# PART_2.net
KiCad netlist of a schematic drawn in Altium Designer
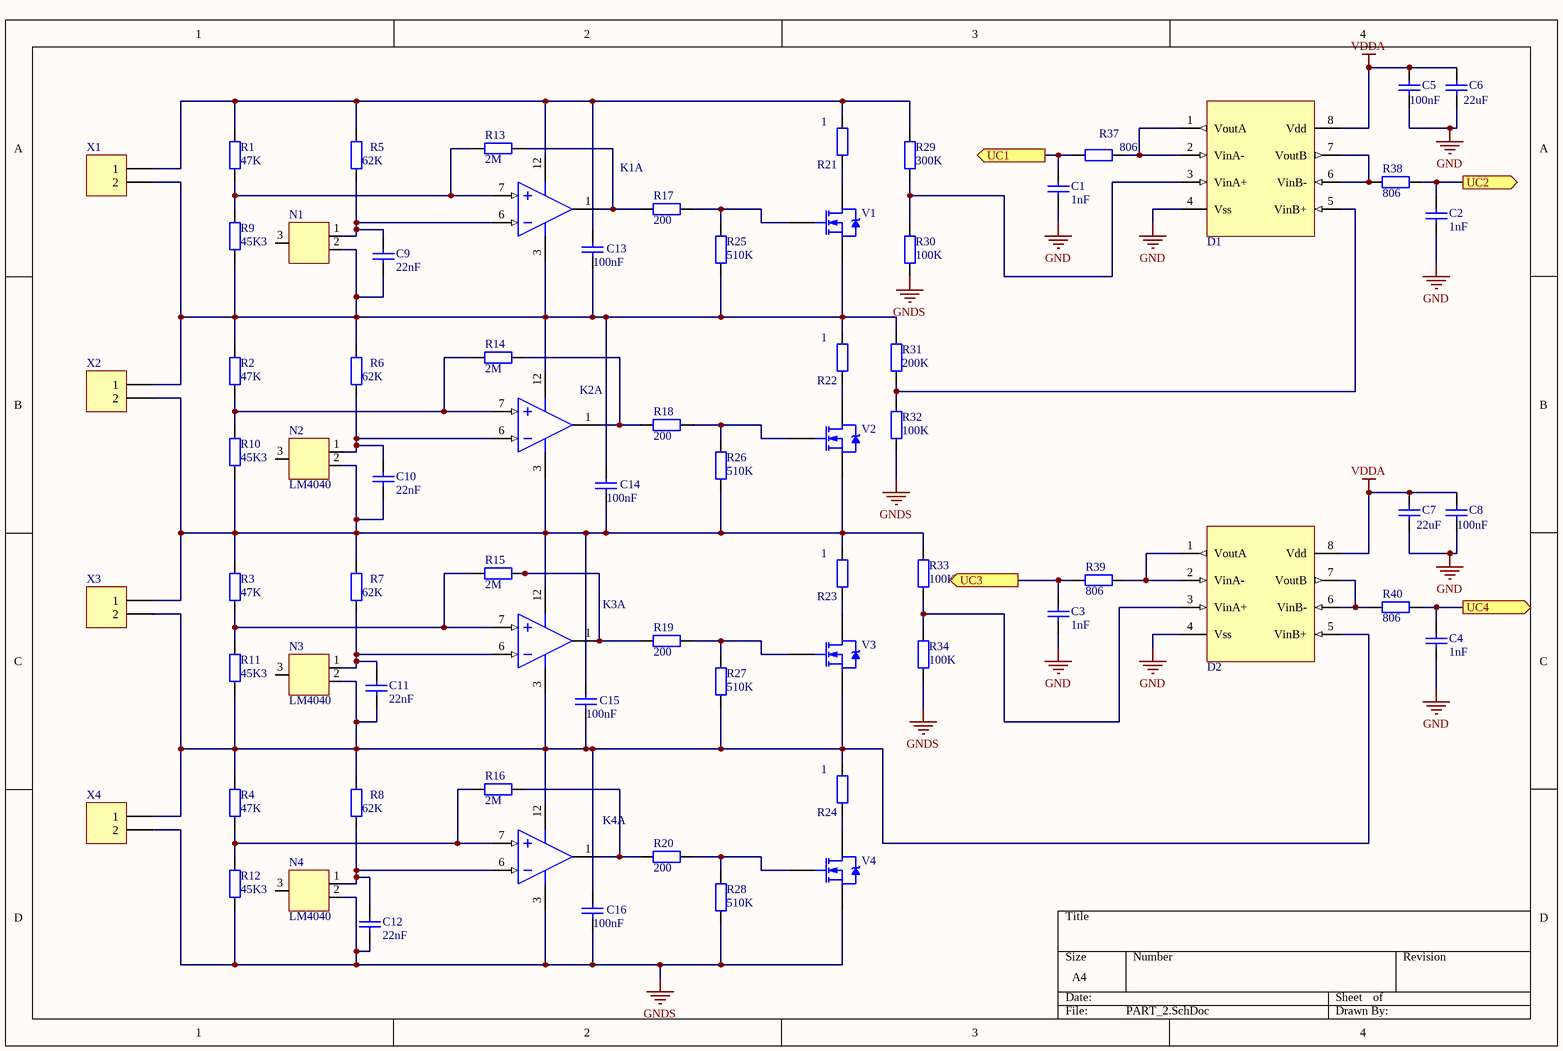
[diagram p0: PART_2.SchDoc]

(export (version "E")
  (design (tool "Eeschema 10.0.6"))
  (components
    (comp (ref "C1")
      (value "1nF")
      (footprint "C0805")
      (description "Capacitor")
      (fields (field (name "Comment") "Cap"))
      (libsource (lib "Miscellaneous Devices") (part "Cap"))
    )
    (comp (ref "C2")
      (value "1nF")
      (footprint "C0805")
      (description "Capacitor")
      (fields (field (name "Comment") "Cap"))
      (libsource (lib "Miscellaneous Devices") (part "Cap"))
    )
    (comp (ref "C3")
      (value "1nF")
      (footprint "C0805")
      (description "Capacitor")
      (fields (field (name "Comment") "Cap"))
      (libsource (lib "Miscellaneous Devices") (part "Cap"))
    )
    (comp (ref "C4")
      (value "1nF")
      (footprint "C0805")
      (description "Capacitor")
      (fields (field (name "Comment") "Cap"))
      (libsource (lib "Miscellaneous Devices") (part "Cap"))
    )
    (comp (ref "C5")
      (value "100nF")
      (footprint "C0805")
      (description "Capacitor")
      (libsource (lib "Miscellaneous Devices") (part "Cap"))
    )
    (comp (ref "C6")
      (value "22uF")
      (footprint "C0805")
      (description "Capacitor")
      (libsource (lib "Miscellaneous Devices") (part "Cap"))
    )
    (comp (ref "C7")
      (value "22uF")
      (footprint "C0805")
      (description "Capacitor")
      (libsource (lib "Miscellaneous Devices") (part "Cap"))
    )
    (comp (ref "C8")
      (value "100nF")
      (footprint "C0805")
      (description "Capacitor")
      (libsource (lib "Miscellaneous Devices") (part "Cap"))
    )
    (comp (ref "C9")
      (value "22nF")
      (footprint "C0805")
      (description "Capacitor")
      (fields (field (name "Comment") "Cap"))
      (libsource (lib "Miscellaneous Devices") (part "Cap"))
    )
    (comp (ref "C10")
      (value "22nF")
      (footprint "C0805")
      (description "Capacitor")
      (fields (field (name "Comment") "Cap"))
      (libsource (lib "Miscellaneous Devices") (part "Cap"))
    )
    (comp (ref "C11")
      (value "22nF")
      (footprint "C0805")
      (description "Capacitor")
      (fields (field (name "Comment") "Cap"))
      (libsource (lib "Miscellaneous Devices") (part "Cap"))
    )
    (comp (ref "C12")
      (value "22nF")
      (footprint "C0805")
      (description "Capacitor")
      (fields (field (name "Comment") "Cap"))
      (libsource (lib "Miscellaneous Devices") (part "Cap"))
    )
    (comp (ref "C13")
      (value "100nF")
      (footprint "C0805")
      (description "Capacitor")
      (fields (field (name "Comment") "Cap"))
      (libsource (lib "Miscellaneous Devices") (part "Cap"))
    )
    (comp (ref "C14")
      (value "100nF")
      (footprint "C0805")
      (description "Capacitor")
      (fields (field (name "Comment") "Cap"))
      (libsource (lib "Miscellaneous Devices") (part "Cap"))
    )
    (comp (ref "C15")
      (value "100nF")
      (footprint "C0805")
      (description "Capacitor")
      (fields (field (name "Comment") "Cap"))
      (libsource (lib "Miscellaneous Devices") (part "Cap"))
    )
    (comp (ref "C16")
      (value "100nF")
      (footprint "C0805")
      (description "Capacitor")
      (fields (field (name "Comment") "Cap"))
      (libsource (lib "Miscellaneous Devices") (part "Cap"))
    )
    (comp (ref "D1")
      (value "~")
      (footprint "MSOP za op.pojacalo")
      (libsource (lib "komponente") (part "Amplifier"))
    )
    (comp (ref "D2")
      (value "~")
      (footprint "MSOP za op.pojacalo")
      (libsource (lib "komponente") (part "Amplifier"))
    )
    (comp (ref "K1")
      (value "TLC3704QJ")
      (footprint "TSSOP5-3")
      (description "Low Power Quad Differential Comparator")
      (libsource (lib "TI Analog Comparator") (part "LP2901D"))
    )
    (comp (ref "K2")
      (value "TLC3704QJ")
      (footprint "TSSOP5-3")
      (description "Low Power Quad Differential Comparator")
      (libsource (lib "TI Analog Comparator") (part "LP2901D"))
    )
    (comp (ref "K3")
      (value "TLC3704QJ")
      (footprint "TSSOP5-3")
      (description "Low Power Quad Differential Comparator")
      (libsource (lib "TI Analog Comparator") (part "LP2901D"))
    )
    (comp (ref "K4")
      (value "TLC3704QJ")
      (footprint "TSSOP5-3")
      (description "Low Power Quad Differential Comparator")
      (libsource (lib "TI Analog Comparator") (part "LP2901D"))
    )
    (comp (ref "N1")
      (value "~")
      (footprint "SOT-23-ref_chip")
      (libsource (lib "komponente") (part "referentni chip"))
    )
    (comp (ref "N2")
      (value "LM4040")
      (footprint "SOT-23-ref_chip")
      (libsource (lib "komponente") (part "referentni chip"))
    )
    (comp (ref "N3")
      (value "LM4040")
      (footprint "SOT-23-ref_chip")
      (libsource (lib "komponente") (part "referentni chip"))
    )
    (comp (ref "N4")
      (value "LM4040")
      (footprint "SOT-23-ref_chip")
      (libsource (lib "komponente") (part "referentni chip"))
    )
    (comp (ref "R1")
      (value "47K")
      (footprint "C0805")
      (description "Resistor")
      (libsource (lib "") (part "Res2_1"))
    )
    (comp (ref "R2")
      (value "47K")
      (footprint "C0805")
      (description "Resistor")
      (libsource (lib "") (part "Res2_1"))
    )
    (comp (ref "R3")
      (value "47K")
      (footprint "C0805")
      (description "Resistor")
      (libsource (lib "") (part "Res2_1"))
    )
    (comp (ref "R4")
      (value "47K")
      (footprint "C0805")
      (description "Resistor")
      (libsource (lib "") (part "Res2_1"))
    )
    (comp (ref "R5")
      (value "62K")
      (footprint "C0805")
      (description "Resistor")
      (libsource (lib "") (part "Res2_1"))
    )
    (comp (ref "R6")
      (value "62K")
      (footprint "C0805")
      (description "Resistor")
      (libsource (lib "") (part "Res2_1"))
    )
    (comp (ref "R7")
      (value "62K")
      (footprint "C0805")
      (description "Resistor")
      (libsource (lib "") (part "Res2_1"))
    )
    (comp (ref "R8")
      (value "62K")
      (footprint "C0805")
      (description "Resistor")
      (libsource (lib "") (part "Res2_1"))
    )
    (comp (ref "R9")
      (value "45K3")
      (footprint "C0805")
      (description "Resistor")
      (libsource (lib "") (part "Res2_1"))
    )
    (comp (ref "R10")
      (value "45K3")
      (footprint "C0805")
      (description "Resistor")
      (libsource (lib "") (part "Res2_1"))
    )
    (comp (ref "R11")
      (value "45K3")
      (footprint "C0805")
      (description "Resistor")
      (libsource (lib "") (part "Res2_1"))
    )
    (comp (ref "R12")
      (value "45K3")
      (footprint "C0805")
      (description "Resistor")
      (libsource (lib "") (part "Res2_1"))
    )
    (comp (ref "R13")
      (value "2M")
      (footprint "C0805")
      (description "Resistor")
      (libsource (lib "Miscellaneous Devices") (part "Res2"))
    )
    (comp (ref "R14")
      (value "2M")
      (footprint "C0805")
      (description "Resistor")
      (libsource (lib "Miscellaneous Devices") (part "Res2"))
    )
    (comp (ref "R15")
      (value "2M")
      (footprint "C0805")
      (description "Resistor")
      (libsource (lib "Miscellaneous Devices") (part "Res2"))
    )
    (comp (ref "R16")
      (value "2M")
      (footprint "C0805")
      (description "Resistor")
      (libsource (lib "Miscellaneous Devices") (part "Res2"))
    )
    (comp (ref "R17")
      (value "200")
      (footprint "C0805")
      (description "Resistor")
      (libsource (lib "Miscellaneous Devices") (part "Res2"))
    )
    (comp (ref "R18")
      (value "200")
      (footprint "C0805")
      (description "Resistor")
      (libsource (lib "Miscellaneous Devices") (part "Res2"))
    )
    (comp (ref "R19")
      (value "200")
      (footprint "C0805")
      (description "Resistor")
      (libsource (lib "Miscellaneous Devices") (part "Res2"))
    )
    (comp (ref "R20")
      (value "200")
      (footprint "C0805")
      (description "Resistor")
      (libsource (lib "Miscellaneous Devices") (part "Res2"))
    )
    (comp (ref "R21")
      (value "1")
      (footprint "F za 7W otpornik")
      (description "Resistor")
      (libsource (lib "") (part "Res2_1"))
    )
    (comp (ref "R22")
      (value "1")
      (footprint "F za 7W otpornik")
      (description "Resistor")
      (libsource (lib "") (part "Res2_1"))
    )
    (comp (ref "R23")
      (value "1")
      (footprint "F za 7W otpornik")
      (description "Resistor")
      (libsource (lib "") (part "Res2_1"))
    )
    (comp (ref "R24")
      (value "1")
      (footprint "F za 7W otpornik")
      (description "Resistor")
      (libsource (lib "") (part "Res2_1"))
    )
    (comp (ref "R25")
      (value "510K")
      (footprint "C0805")
      (description "Resistor")
      (libsource (lib "") (part "Res2_1"))
    )
    (comp (ref "R26")
      (value "510K")
      (footprint "C0805")
      (description "Resistor")
      (libsource (lib "") (part "Res2_1"))
    )
    (comp (ref "R27")
      (value "510K")
      (footprint "C0805")
      (description "Resistor")
      (libsource (lib "") (part "Res2_1"))
    )
    (comp (ref "R28")
      (value "510K")
      (footprint "C0805")
      (description "Resistor")
      (libsource (lib "") (part "Res2_1"))
    )
    (comp (ref "R29")
      (value "300K")
      (footprint "C0805")
      (description "Resistor")
      (libsource (lib "") (part "Res2_1"))
    )
    (comp (ref "R30")
      (value "100K")
      (footprint "C0805")
      (description "Resistor")
      (libsource (lib "") (part "Res2_1"))
    )
    (comp (ref "R31")
      (value "200K")
      (footprint "C0805")
      (description "Resistor")
      (libsource (lib "") (part "Res2_1"))
    )
    (comp (ref "R32")
      (value "100K")
      (footprint "C0805")
      (description "Resistor")
      (libsource (lib "") (part "Res2_1"))
    )
    (comp (ref "R33")
      (value "100K")
      (footprint "C0805")
      (description "Resistor")
      (libsource (lib "") (part "Res2_1"))
    )
    (comp (ref "R34")
      (value "100K")
      (footprint "C0805")
      (description "Resistor")
      (libsource (lib "") (part "Res2_1"))
    )
    (comp (ref "R37")
      (value "806")
      (footprint "C0805")
      (description "Resistor")
      (libsource (lib "Miscellaneous Devices") (part "Res2"))
    )
    (comp (ref "R38")
      (value "806")
      (footprint "C0805")
      (description "Resistor")
      (libsource (lib "") (part "Res2_2"))
    )
    (comp (ref "R39")
      (value "806")
      (footprint "C0805")
      (description "Resistor")
      (libsource (lib "") (part "Res2_2"))
    )
    (comp (ref "R40")
      (value "806")
      (footprint "C0805")
      (description "Resistor")
      (libsource (lib "") (part "Res2_2"))
    )
    (comp (ref "V1")
      (value "NMOS-2")
      (footprint "sot23_transistors")
      (description "N-Channel Power MOSFET")
      (libsource (lib "Miscellaneous Devices") (part "NMOS-2"))
    )
    (comp (ref "V2")
      (value "NMOS-2")
      (footprint "sot23_transistors")
      (description "N-Channel Power MOSFET")
      (libsource (lib "Miscellaneous Devices") (part "NMOS-2"))
    )
    (comp (ref "V3")
      (value "NMOS-2")
      (footprint "sot23_transistors")
      (description "N-Channel Power MOSFET")
      (libsource (lib "Miscellaneous Devices") (part "NMOS-2"))
    )
    (comp (ref "V4")
      (value "NMOS-2")
      (footprint "sot23_transistors")
      (description "N-Channel Power MOSFET")
      (libsource (lib "Miscellaneous Devices") (part "NMOS-2"))
    )
    (comp (ref "X1")
      (value "Header 2")
      (footprint "F Header 1x2")
      (description "Header, 2-Pin")
      (libsource (lib "Miscellaneous Connectors") (part "Header 2"))
    )
    (comp (ref "X2")
      (value "Header 2")
      (footprint "F Header 1x2")
      (description "Header, 2-Pin")
      (libsource (lib "Miscellaneous Connectors") (part "Header 2"))
    )
    (comp (ref "X3")
      (value "Header 2")
      (footprint "F Header 1x2")
      (description "Header, 2-Pin")
      (libsource (lib "Miscellaneous Connectors") (part "Header 2"))
    )
    (comp (ref "X4")
      (value "Header 2")
      (footprint "F Header 1x2")
      (description "Header, 2-Pin")
      (libsource (lib "Miscellaneous Connectors") (part "Header 2"))
    )
  )
  (nets
    (net (code "1") (name "/UC1") (class "Default")
      (node (ref "C1") (pin "2") (pinfunction "2_2") (pintype "passive"))
      (node (ref "R37") (pin "2") (pinfunction "2_2") (pintype "passive"))
    )
    (net (code "2") (name "/UC2") (class "Default")
      (node (ref "C2") (pin "2") (pinfunction "2_2") (pintype "passive"))
      (node (ref "R38") (pin "2") (pinfunction "2_2") (pintype "passive"))
    )
    (net (code "3") (name "/UC3") (class "Default")
      (node (ref "C3") (pin "2") (pinfunction "2_2") (pintype "passive"))
      (node (ref "R39") (pin "1") (pinfunction "1_1") (pintype "passive"))
    )
    (net (code "4") (name "/UC4") (class "Default")
      (node (ref "C4") (pin "2") (pinfunction "2_2") (pintype "passive"))
      (node (ref "R40") (pin "2") (pinfunction "2_2") (pintype "passive"))
    )
    (net (code "5") (name "GND") (class "Default")
      (node (ref "C1") (pin "1") (pinfunction "1_1") (pintype "passive"))
      (node (ref "C2") (pin "1") (pinfunction "1_1") (pintype "passive"))
      (node (ref "C3") (pin "1") (pinfunction "1_1") (pintype "passive"))
      (node (ref "C4") (pin "1") (pinfunction "1_1") (pintype "passive"))
      (node (ref "C5") (pin "1") (pinfunction "1_1") (pintype "passive"))
      (node (ref "C6") (pin "1") (pinfunction "1_1") (pintype "passive"))
      (node (ref "C7") (pin "1") (pinfunction "1_1") (pintype "passive"))
      (node (ref "C8") (pin "1") (pinfunction "1_1") (pintype "passive"))
      (node (ref "D1") (pin "4") (pinfunction "Vss_4") (pintype "power_in"))
      (node (ref "D2") (pin "4") (pinfunction "Vss_4") (pintype "power_in"))
    )
    (net (code "6") (name "GNDS") (class "Default")
      (node (ref "C12") (pin "1") (pinfunction "1_1") (pintype "passive"))
      (node (ref "C16") (pin "2") (pinfunction "2_2") (pintype "passive"))
      (node (ref "K4") (pin "3") (pinfunction "V+_3") (pintype "passive"))
      (node (ref "N4") (pin "2") (pinfunction "2_2") (pintype "passive"))
      (node (ref "R12") (pin "1") (pinfunction "1_1") (pintype "passive"))
      (node (ref "R28") (pin "1") (pinfunction "1_1") (pintype "passive"))
      (node (ref "R30") (pin "1") (pinfunction "1_1") (pintype "passive"))
      (node (ref "R32") (pin "1") (pinfunction "1_1") (pintype "passive"))
      (node (ref "R34") (pin "1") (pinfunction "1_1") (pintype "passive"))
      (node (ref "V4") (pin "3") (pinfunction "S_3") (pintype "passive"))
      (node (ref "X4") (pin "2") (pinfunction "2_2") (pintype "passive"))
    )
    (net (code "7") (name "Net-(D1-VinA+)") (class "Default")
      (node (ref "D1") (pin "3") (pinfunction "VinA+_3") (pintype "input"))
      (node (ref "R29") (pin "1") (pinfunction "1_1") (pintype "passive"))
      (node (ref "R30") (pin "2") (pinfunction "2_2") (pintype "passive"))
    )
    (net (code "8") (name "Net-(D1-VinA-)") (class "Default")
      (node (ref "D1") (pin "1") (pinfunction "VoutA_1") (pintype "output"))
      (node (ref "D1") (pin "2") (pinfunction "VinA-_2") (pintype "input"))
      (node (ref "R37") (pin "1") (pinfunction "1_1") (pintype "passive"))
    )
    (net (code "9") (name "Net-(D1-VinB+)") (class "Default")
      (node (ref "D1") (pin "5") (pinfunction "VinB+_5") (pintype "input"))
      (node (ref "R31") (pin "1") (pinfunction "1_1") (pintype "passive"))
      (node (ref "R32") (pin "2") (pinfunction "2_2") (pintype "passive"))
    )
    (net (code "10") (name "Net-(D1-VinB-)") (class "Default")
      (node (ref "D1") (pin "6") (pinfunction "VinB-_6") (pintype "input"))
      (node (ref "D1") (pin "7") (pinfunction "VoutB_7") (pintype "output"))
      (node (ref "R38") (pin "1") (pinfunction "1_1") (pintype "passive"))
    )
    (net (code "11") (name "Net-(D2-VinA+)") (class "Default")
      (node (ref "D2") (pin "3") (pinfunction "VinA+_3") (pintype "input"))
      (node (ref "R33") (pin "1") (pinfunction "1_1") (pintype "passive"))
      (node (ref "R34") (pin "2") (pinfunction "2_2") (pintype "passive"))
    )
    (net (code "12") (name "Net-(D2-VinA-)") (class "Default")
      (node (ref "D2") (pin "1") (pinfunction "VoutA_1") (pintype "output"))
      (node (ref "D2") (pin "2") (pinfunction "VinA-_2") (pintype "input"))
      (node (ref "R39") (pin "2") (pinfunction "2_2") (pintype "passive"))
    )
    (net (code "13") (name "Net-(D2-VinB+)") (class "Default")
      (node (ref "C11") (pin "1") (pinfunction "1_1") (pintype "passive"))
      (node (ref "C15") (pin "2") (pinfunction "2_2") (pintype "passive"))
      (node (ref "C16") (pin "1") (pinfunction "1_1") (pintype "passive"))
      (node (ref "D2") (pin "5") (pinfunction "VinB+_5") (pintype "input"))
      (node (ref "K3") (pin "3") (pinfunction "V+_3") (pintype "passive"))
      (node (ref "K4") (pin "12") (pinfunction "V-_12") (pintype "passive"))
      (node (ref "N3") (pin "2") (pinfunction "2_2") (pintype "passive"))
      (node (ref "R11") (pin "1") (pinfunction "1_1") (pintype "passive"))
      (node (ref "R24") (pin "2") (pinfunction "2_2") (pintype "passive"))
      (node (ref "R27") (pin "1") (pinfunction "1_1") (pintype "passive"))
      (node (ref "R4") (pin "2") (pinfunction "2_2") (pintype "passive"))
      (node (ref "R8") (pin "2") (pinfunction "2_2") (pintype "passive"))
      (node (ref "V3") (pin "3") (pinfunction "S_3") (pintype "passive"))
      (node (ref "X3") (pin "2") (pinfunction "2_2") (pintype "passive"))
      (node (ref "X4") (pin "1") (pinfunction "1_1") (pintype "passive"))
    )
    (net (code "14") (name "Net-(D2-VinB-)") (class "Default")
      (node (ref "D2") (pin "6") (pinfunction "VinB-_6") (pintype "input"))
      (node (ref "D2") (pin "7") (pinfunction "VoutB_7") (pintype "output"))
      (node (ref "R40") (pin "1") (pinfunction "1_1") (pintype "passive"))
    )
    (net (code "15") (name "Net-(K1A-IN+)") (class "Default")
      (node (ref "K1") (pin "7") (pinfunction "IN+_7") (pintype "input"))
      (node (ref "R1") (pin "1") (pinfunction "1_1") (pintype "passive"))
      (node (ref "R13") (pin "2") (pinfunction "2_2") (pintype "passive"))
      (node (ref "R9") (pin "2") (pinfunction "2_2") (pintype "passive"))
    )
    (net (code "16") (name "Net-(K1A-IN-)") (class "Default")
      (node (ref "C9") (pin "2") (pinfunction "2_2") (pintype "passive"))
      (node (ref "K1") (pin "6") (pinfunction "IN-_6") (pintype "input"))
      (node (ref "N1") (pin "1") (pinfunction "1_1") (pintype "bidirectional"))
      (node (ref "R5") (pin "1") (pinfunction "1_1") (pintype "passive"))
    )
    (net (code "17") (name "Net-(K1A-OUT)") (class "Default")
      (node (ref "K1") (pin "1") (pinfunction "OUT_1") (pintype "open_collector"))
      (node (ref "R13") (pin "1") (pinfunction "1_1") (pintype "passive"))
      (node (ref "R17") (pin "2") (pinfunction "2_2") (pintype "passive"))
    )
    (net (code "18") (name "Net-(K1A-V+)") (class "Default")
      (node (ref "C13") (pin "2") (pinfunction "2_2") (pintype "passive"))
      (node (ref "C14") (pin "1") (pinfunction "1_1") (pintype "passive"))
      (node (ref "C9") (pin "1") (pinfunction "1_1") (pintype "passive"))
      (node (ref "K1") (pin "3") (pinfunction "V+_3") (pintype "passive"))
      (node (ref "K2") (pin "12") (pinfunction "V-_12") (pintype "passive"))
      (node (ref "N1") (pin "2") (pinfunction "2_2") (pintype "passive"))
      (node (ref "R2") (pin "2") (pinfunction "2_2") (pintype "passive"))
      (node (ref "R22") (pin "2") (pinfunction "2_2") (pintype "passive"))
      (node (ref "R25") (pin "1") (pinfunction "1_1") (pintype "passive"))
      (node (ref "R31") (pin "2") (pinfunction "2_2") (pintype "passive"))
      (node (ref "R6") (pin "2") (pinfunction "2_2") (pintype "passive"))
      (node (ref "R9") (pin "1") (pinfunction "1_1") (pintype "passive"))
      (node (ref "V1") (pin "3") (pinfunction "S_3") (pintype "passive"))
      (node (ref "X1") (pin "2") (pinfunction "2_2") (pintype "passive"))
      (node (ref "X2") (pin "1") (pinfunction "1_1") (pintype "passive"))
    )
    (net (code "19") (name "Net-(K1A-V-)") (class "Default")
      (node (ref "C13") (pin "1") (pinfunction "1_1") (pintype "passive"))
      (node (ref "K1") (pin "12") (pinfunction "V-_12") (pintype "passive"))
      (node (ref "R1") (pin "2") (pinfunction "2_2") (pintype "passive"))
      (node (ref "R21") (pin "2") (pinfunction "2_2") (pintype "passive"))
      (node (ref "R29") (pin "2") (pinfunction "2_2") (pintype "passive"))
      (node (ref "R5") (pin "2") (pinfunction "2_2") (pintype "passive"))
      (node (ref "X1") (pin "1") (pinfunction "1_1") (pintype "passive"))
    )
    (net (code "20") (name "Net-(K2A-IN+)") (class "Default")
      (node (ref "K2") (pin "7") (pinfunction "IN+_7") (pintype "input"))
      (node (ref "R10") (pin "2") (pinfunction "2_2") (pintype "passive"))
      (node (ref "R14") (pin "2") (pinfunction "2_2") (pintype "passive"))
      (node (ref "R2") (pin "1") (pinfunction "1_1") (pintype "passive"))
    )
    (net (code "21") (name "Net-(K2A-IN-)") (class "Default")
      (node (ref "C10") (pin "2") (pinfunction "2_2") (pintype "passive"))
      (node (ref "K2") (pin "6") (pinfunction "IN-_6") (pintype "input"))
      (node (ref "N2") (pin "1") (pinfunction "1_1") (pintype "bidirectional"))
      (node (ref "R6") (pin "1") (pinfunction "1_1") (pintype "passive"))
    )
    (net (code "22") (name "Net-(K2A-OUT)") (class "Default")
      (node (ref "K2") (pin "1") (pinfunction "OUT_1") (pintype "open_collector"))
      (node (ref "R14") (pin "1") (pinfunction "1_1") (pintype "passive"))
      (node (ref "R18") (pin "2") (pinfunction "2_2") (pintype "passive"))
    )
    (net (code "23") (name "Net-(K2A-V+)") (class "Default")
      (node (ref "C10") (pin "1") (pinfunction "1_1") (pintype "passive"))
      (node (ref "C14") (pin "2") (pinfunction "2_2") (pintype "passive"))
      (node (ref "C15") (pin "1") (pinfunction "1_1") (pintype "passive"))
      (node (ref "K2") (pin "3") (pinfunction "V+_3") (pintype "passive"))
      (node (ref "K3") (pin "12") (pinfunction "V-_12") (pintype "passive"))
      (node (ref "N2") (pin "2") (pinfunction "2_2") (pintype "passive"))
      (node (ref "R10") (pin "1") (pinfunction "1_1") (pintype "passive"))
      (node (ref "R23") (pin "2") (pinfunction "2_2") (pintype "passive"))
      (node (ref "R26") (pin "1") (pinfunction "1_1") (pintype "passive"))
      (node (ref "R3") (pin "2") (pinfunction "2_2") (pintype "passive"))
      (node (ref "R33") (pin "2") (pinfunction "2_2") (pintype "passive"))
      (node (ref "R7") (pin "2") (pinfunction "2_2") (pintype "passive"))
      (node (ref "V2") (pin "3") (pinfunction "S_3") (pintype "passive"))
      (node (ref "X2") (pin "2") (pinfunction "2_2") (pintype "passive"))
      (node (ref "X3") (pin "1") (pinfunction "1_1") (pintype "passive"))
    )
    (net (code "24") (name "Net-(K3A-IN+)") (class "Default")
      (node (ref "K3") (pin "7") (pinfunction "IN+_7") (pintype "input"))
      (node (ref "R11") (pin "2") (pinfunction "2_2") (pintype "passive"))
      (node (ref "R15") (pin "2") (pinfunction "2_2") (pintype "passive"))
      (node (ref "R3") (pin "1") (pinfunction "1_1") (pintype "passive"))
    )
    (net (code "25") (name "Net-(K3A-IN-)") (class "Default")
      (node (ref "C11") (pin "2") (pinfunction "2_2") (pintype "passive"))
      (node (ref "K3") (pin "6") (pinfunction "IN-_6") (pintype "input"))
      (node (ref "N3") (pin "1") (pinfunction "1_1") (pintype "bidirectional"))
      (node (ref "R7") (pin "1") (pinfunction "1_1") (pintype "passive"))
    )
    (net (code "26") (name "Net-(K3A-OUT)") (class "Default")
      (node (ref "K3") (pin "1") (pinfunction "OUT_1") (pintype "open_collector"))
      (node (ref "R15") (pin "1") (pinfunction "1_1") (pintype "passive"))
      (node (ref "R19") (pin "2") (pinfunction "2_2") (pintype "passive"))
    )
    (net (code "27") (name "Net-(K4A-IN+)") (class "Default")
      (node (ref "K4") (pin "7") (pinfunction "IN+_7") (pintype "input"))
      (node (ref "R12") (pin "2") (pinfunction "2_2") (pintype "passive"))
      (node (ref "R16") (pin "2") (pinfunction "2_2") (pintype "passive"))
      (node (ref "R4") (pin "1") (pinfunction "1_1") (pintype "passive"))
    )
    (net (code "28") (name "Net-(K4A-IN-)") (class "Default")
      (node (ref "C12") (pin "2") (pinfunction "2_2") (pintype "passive"))
      (node (ref "K4") (pin "6") (pinfunction "IN-_6") (pintype "input"))
      (node (ref "N4") (pin "1") (pinfunction "1_1") (pintype "bidirectional"))
      (node (ref "R8") (pin "1") (pinfunction "1_1") (pintype "passive"))
    )
    (net (code "29") (name "Net-(K4A-OUT)") (class "Default")
      (node (ref "K4") (pin "1") (pinfunction "OUT_1") (pintype "open_collector"))
      (node (ref "R16") (pin "1") (pinfunction "1_1") (pintype "passive"))
      (node (ref "R20") (pin "2") (pinfunction "2_2") (pintype "passive"))
    )
    (net (code "30") (name "Net-(V1-D)") (class "Default")
      (node (ref "R21") (pin "1") (pinfunction "1_1") (pintype "passive"))
      (node (ref "V1") (pin "2") (pinfunction "D_2") (pintype "passive"))
    )
    (net (code "31") (name "Net-(V1-G)") (class "Default")
      (node (ref "R17") (pin "1") (pinfunction "1_1") (pintype "passive"))
      (node (ref "R25") (pin "2") (pinfunction "2_2") (pintype "passive"))
      (node (ref "V1") (pin "1") (pinfunction "G_1") (pintype "passive"))
    )
    (net (code "32") (name "Net-(V2-D)") (class "Default")
      (node (ref "R22") (pin "1") (pinfunction "1_1") (pintype "passive"))
      (node (ref "V2") (pin "2") (pinfunction "D_2") (pintype "passive"))
    )
    (net (code "33") (name "Net-(V2-G)") (class "Default")
      (node (ref "R18") (pin "1") (pinfunction "1_1") (pintype "passive"))
      (node (ref "R26") (pin "2") (pinfunction "2_2") (pintype "passive"))
      (node (ref "V2") (pin "1") (pinfunction "G_1") (pintype "passive"))
    )
    (net (code "34") (name "Net-(V3-D)") (class "Default")
      (node (ref "R23") (pin "1") (pinfunction "1_1") (pintype "passive"))
      (node (ref "V3") (pin "2") (pinfunction "D_2") (pintype "passive"))
    )
    (net (code "35") (name "Net-(V3-G)") (class "Default")
      (node (ref "R19") (pin "1") (pinfunction "1_1") (pintype "passive"))
      (node (ref "R27") (pin "2") (pinfunction "2_2") (pintype "passive"))
      (node (ref "V3") (pin "1") (pinfunction "G_1") (pintype "passive"))
    )
    (net (code "36") (name "Net-(V4-D)") (class "Default")
      (node (ref "R24") (pin "1") (pinfunction "1_1") (pintype "passive"))
      (node (ref "V4") (pin "2") (pinfunction "D_2") (pintype "passive"))
    )
    (net (code "37") (name "Net-(V4-G)") (class "Default")
      (node (ref "R20") (pin "1") (pinfunction "1_1") (pintype "passive"))
      (node (ref "R28") (pin "2") (pinfunction "2_2") (pintype "passive"))
      (node (ref "V4") (pin "1") (pinfunction "G_1") (pintype "passive"))
    )
    (net (code "38") (name "VDDA") (class "Default")
      (node (ref "C5") (pin "2") (pinfunction "2_2") (pintype "passive"))
      (node (ref "C6") (pin "2") (pinfunction "2_2") (pintype "passive"))
      (node (ref "C7") (pin "2") (pinfunction "2_2") (pintype "passive"))
      (node (ref "C8") (pin "2") (pinfunction "2_2") (pintype "passive"))
      (node (ref "D1") (pin "8") (pinfunction "Vdd_8") (pintype "power_in"))
      (node (ref "D2") (pin "8") (pinfunction "Vdd_8") (pintype "power_in"))
    )
    (net (code "39") (name "unconnected-(N1-Pad3)") (class "Default")
      (node (ref "N1") (pin "3") (pinfunction "3_3") (pintype "passive"))
    )
    (net (code "40") (name "unconnected-(N2-Pad3)") (class "Default")
      (node (ref "N2") (pin "3") (pinfunction "3_3") (pintype "passive"))
    )
    (net (code "41") (name "unconnected-(N3-Pad3)") (class "Default")
      (node (ref "N3") (pin "3") (pinfunction "3_3") (pintype "passive"))
    )
    (net (code "42") (name "unconnected-(N4-Pad3)") (class "Default")
      (node (ref "N4") (pin "3") (pinfunction "3_3") (pintype "passive"))
    )
    (net (code "43") (name "unconnected-(V1-S-Pad3)") (class "Default")
      (node (ref "V1") (pin "3") (pinfunction "S_3") (pintype "passive"))
    )
    (net (code "44") (name "unconnected-(V1-S-Pad3)_1") (class "Default")
      (node (ref "V1") (pin "3") (pinfunction "S_3") (pintype "passive"))
    )
    (net (code "45") (name "unconnected-(V2-S-Pad3)") (class "Default")
      (node (ref "V2") (pin "3") (pinfunction "S_3") (pintype "passive"))
    )
    (net (code "46") (name "unconnected-(V2-S-Pad3)_1") (class "Default")
      (node (ref "V2") (pin "3") (pinfunction "S_3") (pintype "passive"))
    )
    (net (code "47") (name "unconnected-(V3-S-Pad3)") (class "Default")
      (node (ref "V3") (pin "3") (pinfunction "S_3") (pintype "passive"))
    )
    (net (code "48") (name "unconnected-(V3-S-Pad3)_1") (class "Default")
      (node (ref "V3") (pin "3") (pinfunction "S_3") (pintype "passive"))
    )
    (net (code "49") (name "unconnected-(V4-S-Pad3)") (class "Default")
      (node (ref "V4") (pin "3") (pinfunction "S_3") (pintype "passive"))
    )
    (net (code "50") (name "unconnected-(V4-S-Pad3)_1") (class "Default")
      (node (ref "V4") (pin "3") (pinfunction "S_3") (pintype "passive"))
    )
  )
)
